# POWER.net
KiCad netlist of a schematic drawn in Altium Designer
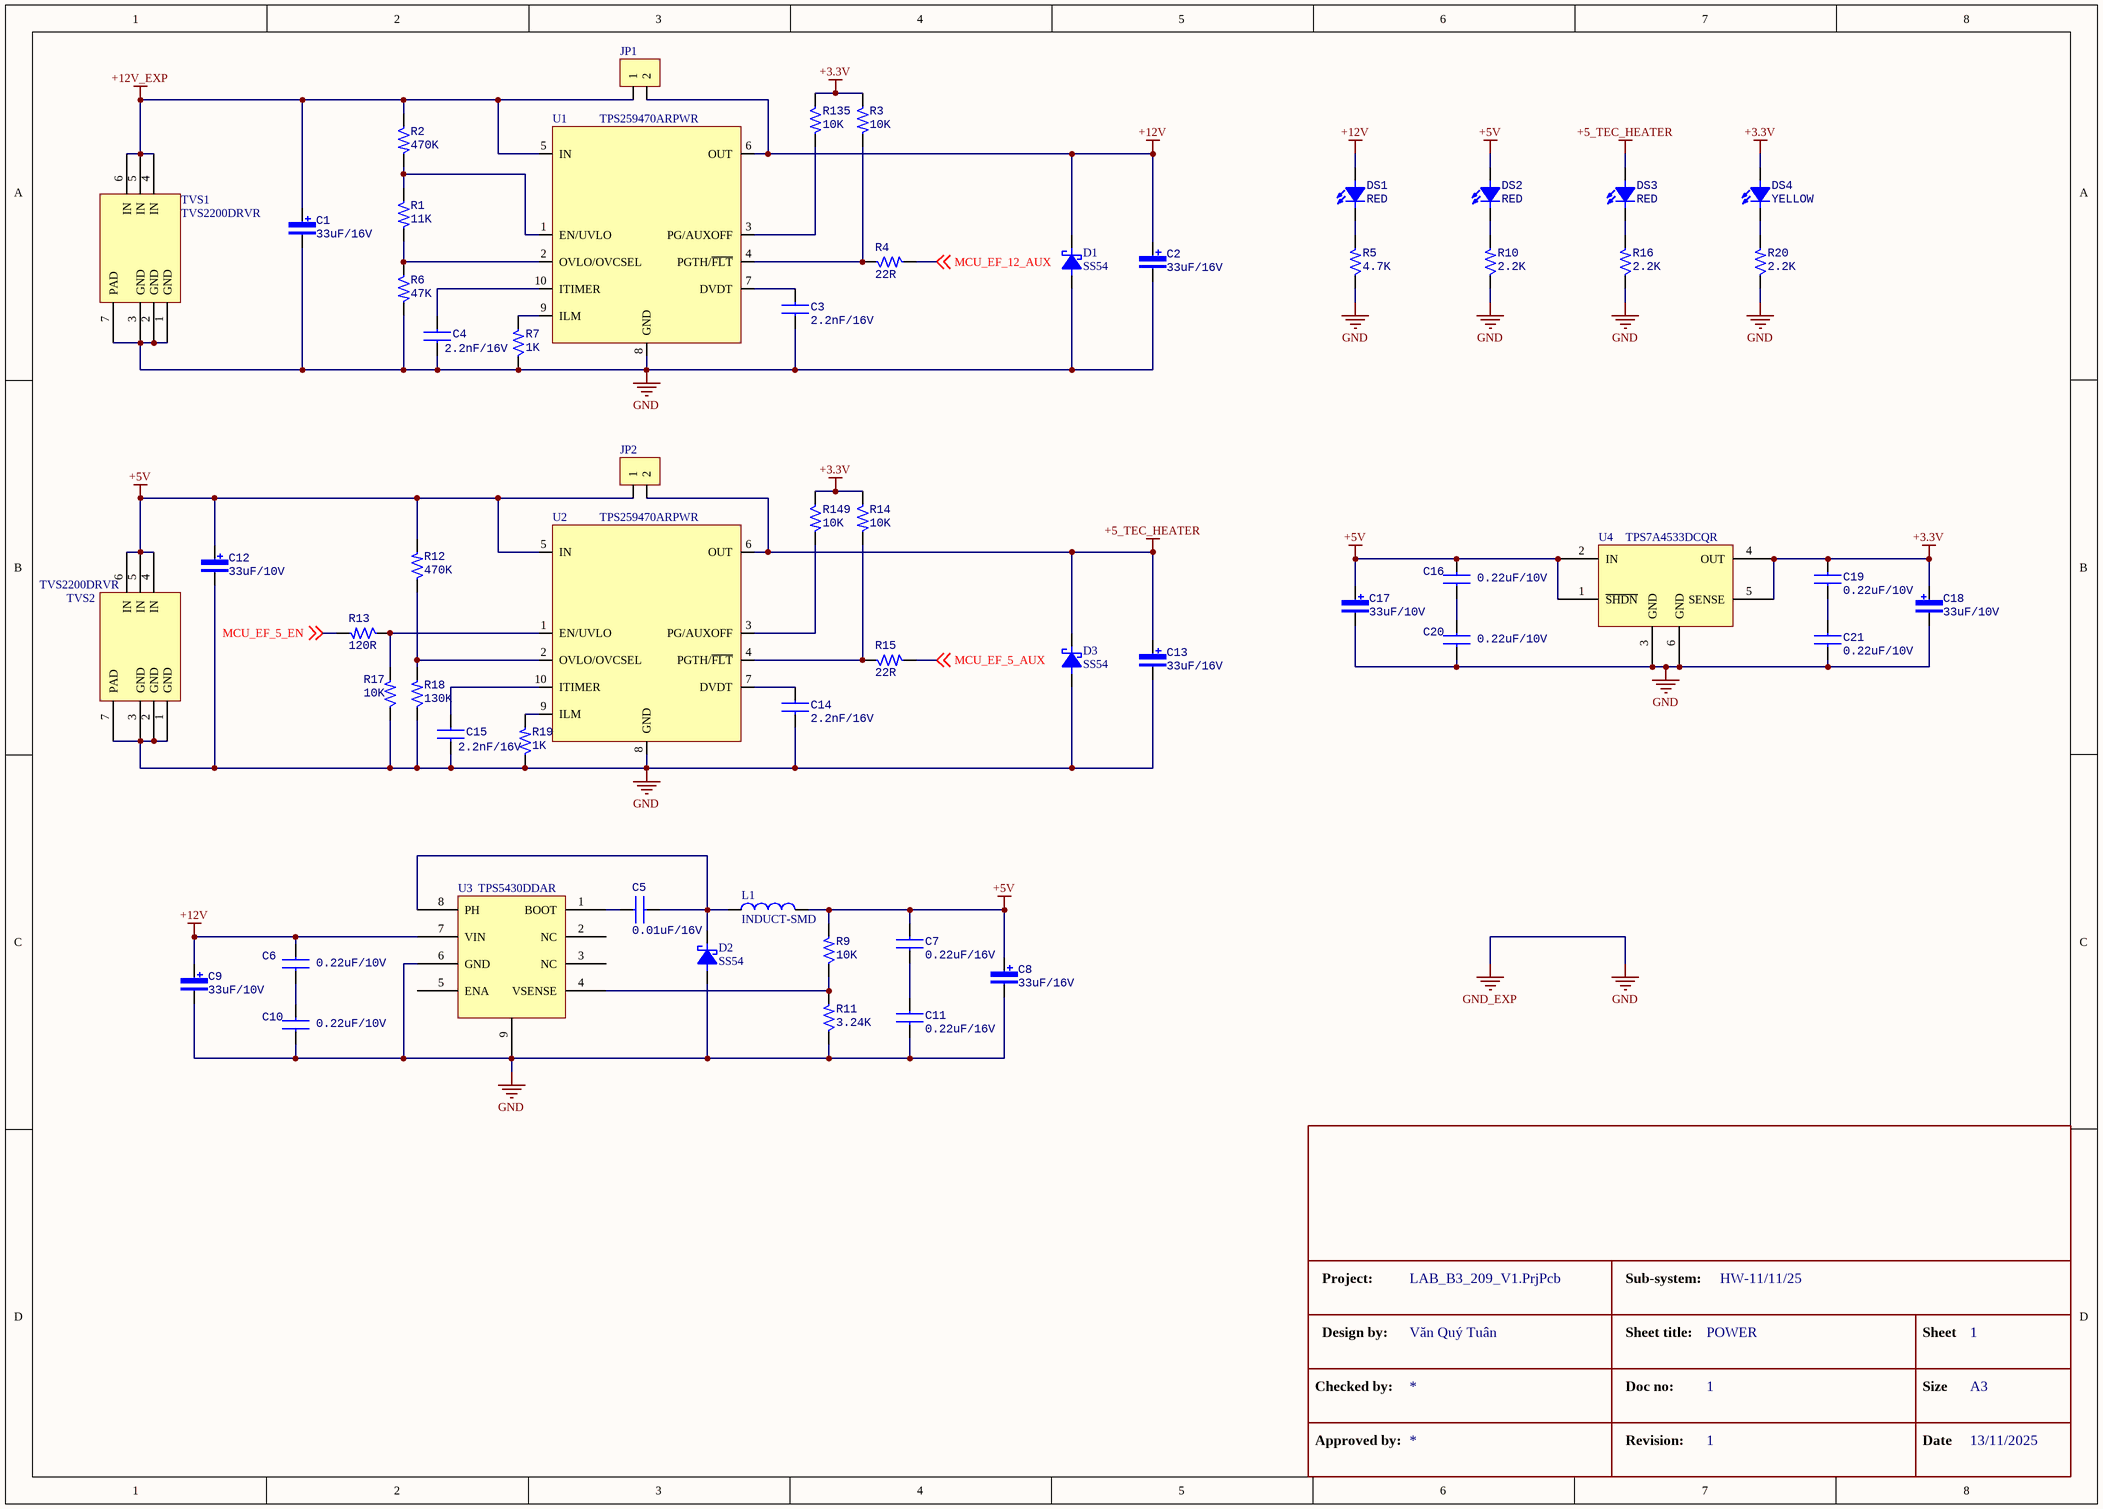
[diagram p0: POWER.SchDoc]

(export (version "E")
  (design (tool "Eeschema 10.0.6"))
  (components
    (comp (ref "C1") (value "33uF/16V") (footprint "CAP-TAN-2312") (libsource (lib "") (part "CAP-TAN_1")))
    (comp (ref "C2") (value "33uF/16V") (footprint "CAP-TAN-2312") (libsource (lib "") (part "CAP-TAN_1")))
    (comp (ref "C3") (value "2.2nF/16V") (footprint "CAP-CER-0603") (libsource (lib "ID") (part "CAP-CER")))
    (comp (ref "C4") (value "2.2nF/16V") (footprint "CAP-CER-0603") (libsource (lib "ID") (part "CAP-CER")))
    (comp (ref "C5") (value "0.01uF/16V") (footprint "CAP-CER-0603") (libsource (lib "ID") (part "CAP-CER")))
    (comp (ref "C6") (value "0.22uF/10V") (footprint "CAP-CER-0603") (libsource (lib "ID") (part "CAP-CER")))
    (comp (ref "C7") (value "0.22uF/16V") (footprint "CAP-CER-0603") (libsource (lib "ID") (part "CAP-CER")))
    (comp (ref "C8") (value "33uF/16V") (footprint "CAP-TAN-2312") (libsource (lib "") (part "CAP-TAN_1")))
    (comp (ref "C9") (value "33uF/10V") (footprint "CAP-TAN-2312") (libsource (lib "") (part "CAP-TAN_1")))
    (comp (ref "C10") (value "0.22uF/10V") (footprint "CAP-CER-0603") (libsource (lib "ID") (part "CAP-CER")))
    (comp (ref "C11") (value "0.22uF/16V") (footprint "CAP-CER-0603") (libsource (lib "ID") (part "CAP-CER")))
    (comp (ref "C12") (value "33uF/10V") (footprint "CAP-TAN-2312") (libsource (lib "") (part "CAP-TAN_1")))
    (comp (ref "C13") (value "33uF/16V") (footprint "CAP-TAN-2312") (libsource (lib "") (part "CAP-TAN_1")))
    (comp (ref "C14") (value "2.2nF/16V") (footprint "CAP-CER-0603") (libsource (lib "ID") (part "CAP-CER")))
    (comp (ref "C15") (value "2.2nF/16V") (footprint "CAP-CER-0603") (libsource (lib "ID") (part "CAP-CER")))
    (comp (ref "C16") (value "0.22uF/10V") (footprint "CAP-CER-0603") (libsource (lib "ID") (part "CAP-CER")))
    (comp (ref "C17") (value "33uF/10V") (footprint "CAP-TAN-2312") (libsource (lib "") (part "CAP-TAN_1")))
    (comp (ref "C18") (value "33uF/10V") (footprint "CAP-TAN-2312") (libsource (lib "ID") (part "CAP-TAN")))
    (comp (ref "C19") (value "0.22uF/10V") (footprint "CAP-CER-0603") (libsource (lib "ID") (part "CAP-CER")))
    (comp (ref "C20") (value "0.22uF/10V") (footprint "CAP-CER-0603") (libsource (lib "ID") (part "CAP-CER")))
    (comp (ref "C21") (value "0.22uF/10V") (footprint "CAP-CER-0603") (libsource (lib "ID") (part "CAP-CER")))
    (comp (ref "D1") (value "SS54") (footprint "DIODE SMA") (libsource (lib "ID") (part "DIODE-SCHOTTKY")))
    (comp (ref "D2") (value "SS54") (footprint "DIODE SMA") (libsource (lib "ID") (part "DIODE-SCHOTTKY")))
    (comp (ref "D3") (value "SS54") (footprint "DIODE SMA") (libsource (lib "ID") (part "DIODE-SCHOTTKY")))
    (comp (ref "DS1") (value "RED") (footprint "LED-SMD-0603") (libsource (lib "ID") (part "LED")))
    (comp (ref "DS2") (value "RED") (footprint "LED-SMD-0603") (libsource (lib "ID") (part "LED")))
    (comp (ref "DS3") (value "RED") (footprint "LED-SMD-0603") (libsource (lib "ID") (part "LED")))
    (comp (ref "DS4") (value "YELLOW") (footprint "LED-SMD-0603") (libsource (lib "ID") (part "LED")))
    (comp (ref "JP1")
      (value "JP 1x2 2.54")
      (footprint "JP 1x2 DT")
      (description "Cắm")
      (libsource (lib "Jump") (part "JP 1x2 2.54 Duc Thang"))
    )
    (comp (ref "JP2")
      (value "JP 1x2 2.54")
      (footprint "JP 1x2 DT")
      (description "Cắm")
      (libsource (lib "Jump") (part "JP 1x2 2.54 Duc Thang"))
    )
    (comp (ref "L1")
      (value "INDUCT-SMD")
      (footprint "INDUCTOR-FIXED IND 22UH 2.5A 170 MOHM SMD")
      (fields (field (name "MP") "LQM18PZ2R2MFHD") (field (name "MF") "Murata"))
      (libsource (lib "ID") (part "INDUCT-SMD"))
    )
    (comp (ref "R1") (value "11K") (footprint "RES-SMD-0603") (libsource (lib "ID") (part "RES-SMD")))
    (comp (ref "R2") (value "470K") (footprint "RES-SMD-0603") (libsource (lib "ID") (part "RES-SMD")))
    (comp (ref "R3") (value "10K") (footprint "RES-SMD-0603") (libsource (lib "ID") (part "RES-SMD")))
    (comp (ref "R4") (value "22R") (footprint "RES-SMD-0603") (libsource (lib "ID") (part "RES-SMD")))
    (comp (ref "R5") (value "4.7K") (footprint "RES-SMD-0603") (libsource (lib "ID") (part "RES-SMD")))
    (comp (ref "R6") (value "47K") (footprint "RES-SMD-0603") (libsource (lib "ID") (part "RES-SMD")))
    (comp (ref "R7") (value "1K") (footprint "RES-SMD-0603") (libsource (lib "ID") (part "RES-SMD")))
    (comp (ref "R9") (value "10K") (footprint "RES-SMD-0603") (libsource (lib "ID") (part "RES-SMD")))
    (comp (ref "R10") (value "2.2K") (footprint "RES-SMD-0603") (libsource (lib "ID") (part "RES-SMD")))
    (comp (ref "R11") (value "3.24K") (footprint "RES-SMD-0603") (libsource (lib "ID") (part "RES-SMD")))
    (comp (ref "R12") (value "470K") (footprint "RES-SMD-0603") (libsource (lib "ID") (part "RES-SMD")))
    (comp (ref "R13") (value "120R") (footprint "RES-SMD-0603") (libsource (lib "ID") (part "RES-SMD")))
    (comp (ref "R14") (value "10K") (footprint "RES-SMD-0603") (libsource (lib "ID") (part "RES-SMD")))
    (comp (ref "R15") (value "22R") (footprint "RES-SMD-0603") (libsource (lib "ID") (part "RES-SMD")))
    (comp (ref "R16") (value "2.2K") (footprint "RES-SMD-0603") (libsource (lib "ID") (part "RES-SMD")))
    (comp (ref "R17") (value "10K") (footprint "RES-SMD-0603") (libsource (lib "ID") (part "RES-SMD")))
    (comp (ref "R18") (value "130K") (footprint "RES-SMD-0603") (libsource (lib "ID") (part "RES-SMD")))
    (comp (ref "R19") (value "1K") (footprint "RES-SMD-0603") (libsource (lib "ID") (part "RES-SMD")))
    (comp (ref "R20") (value "2.2K") (footprint "RES-SMD-0603") (libsource (lib "ID") (part "RES-SMD")))
    (comp (ref "R135") (value "10K") (footprint "RES-SMD-0603") (libsource (lib "ID") (part "RES-SMD")))
    (comp (ref "R149") (value "10K") (footprint "RES-SMD-0603") (libsource (lib "ID") (part "RES-SMD")))
    (comp (ref "TVS1")
      (value "TVS2200DRVR")
      (footprint "TVS2200DRVR")
      (libsource (lib "LAB_B3_209_V1") (part "TVS2200DRVR"))
    )
    (comp (ref "TVS2")
      (value "TVS2200DRVR")
      (footprint "TVS2200DRVR")
      (libsource (lib "LAB_B3_209_V1") (part "TVS2200DRVR"))
    )
    (comp (ref "U1")
      (value "TPS259470ARPWR")
      (footprint "VQFN-HR-10")
      (fields
        (field (name "MANUFACTURER") "Texas Instruments")
        (field (name "MANUFACTURER PART NUMBER") "TPS259472ARPWR")
      )
      (libsource (lib "Schematic-Lib-PhilsLab") (part "TPS259472ARPWR"))
    )
    (comp (ref "U2")
      (value "TPS259470ARPWR")
      (footprint "VQFN-HR-10")
      (fields
        (field (name "MANUFACTURER") "Texas Instruments")
        (field (name "MANUFACTURER PART NUMBER") "TPS259472ARPWR")
      )
      (libsource (lib "Schematic-Lib-PhilsLab") (part "TPS259472ARPWR"))
    )
    (comp (ref "U3")
      (value "TPS5430DDAR")
      (footprint "TPS5430DDAR")
      (libsource (lib "LAB_B3_209_V1") (part "TPS5430DDAR"))
    )
    (comp (ref "U4")
      (value "TPS7A4533DCQR")
      (footprint "TPS7A4533DCQR")
      (libsource (lib "LAB_B3_209_V1") (part "TPS7A4533DCQR"))
    )
  )
  (nets
    (net (code "1") (name "+3.3V") (class "Default")
      (node (ref "C18") (pin "1") (pinfunction "1_1") (pintype "passive"))
      (node (ref "C19") (pin "2") (pinfunction "2_2") (pintype "passive"))
      (node (ref "DS4") (pin "A") (pinfunction "A_A") (pintype "passive"))
      (node (ref "R135") (pin "1") (pinfunction "1_1") (pintype "passive"))
      (node (ref "R14") (pin "1") (pinfunction "1_1") (pintype "passive"))
      (node (ref "R149") (pin "1") (pinfunction "1_1") (pintype "passive"))
      (node (ref "R3") (pin "1") (pinfunction "1_1") (pintype "passive"))
      (node (ref "U4") (pin "4") (pinfunction "OUT_4") (pintype "passive"))
      (node (ref "U4") (pin "5") (pinfunction "SENSE_5") (pintype "passive"))
    )
    (net (code "2") (name "+5V") (class "Default")
      (node (ref "C12") (pin "1") (pinfunction "1_1") (pintype "passive"))
      (node (ref "C16") (pin "2") (pinfunction "2_2") (pintype "passive"))
      (node (ref "C17") (pin "1") (pinfunction "1_1") (pintype "passive"))
      (node (ref "C7") (pin "1") (pinfunction "1_1") (pintype "passive"))
      (node (ref "C8") (pin "1") (pinfunction "1_1") (pintype "passive"))
      (node (ref "DS2") (pin "A") (pinfunction "A_A") (pintype "passive"))
      (node (ref "JP2") (pin "1") (pinfunction "1_1") (pintype "passive"))
      (node (ref "L1") (pin "2") (pinfunction "2_2") (pintype "passive"))
      (node (ref "R12") (pin "2") (pinfunction "2_2") (pintype "passive"))
      (node (ref "R9") (pin "2") (pinfunction "2_2") (pintype "passive"))
      (node (ref "TVS2") (pin "4") (pinfunction "IN_4") (pintype "passive"))
      (node (ref "TVS2") (pin "5") (pinfunction "IN_5") (pintype "passive"))
      (node (ref "TVS2") (pin "6") (pinfunction "IN_6") (pintype "passive"))
      (node (ref "U2") (pin "5") (pinfunction "IN_5") (pintype "passive"))
      (node (ref "U4") (pin "1") (pinfunction "~{SHDN}_1") (pintype "passive"))
      (node (ref "U4") (pin "2") (pinfunction "IN_2") (pintype "passive"))
    )
    (net (code "3") (name "+5_TEC_HEATER") (class "Default")
      (node (ref "C13") (pin "1") (pinfunction "1_1") (pintype "passive"))
      (node (ref "D3") (pin "2") (pinfunction "K_2") (pintype "passive"))
      (node (ref "DS3") (pin "A") (pinfunction "A_A") (pintype "passive"))
      (node (ref "JP2") (pin "2") (pinfunction "2_2") (pintype "passive"))
      (node (ref "U2") (pin "6") (pinfunction "OUT_6") (pintype "passive"))
    )
    (net (code "4") (name "+12V") (class "Default")
      (node (ref "C2") (pin "1") (pinfunction "1_1") (pintype "passive"))
      (node (ref "C6") (pin "2") (pinfunction "2_2") (pintype "passive"))
      (node (ref "C9") (pin "1") (pinfunction "1_1") (pintype "passive"))
      (node (ref "D1") (pin "2") (pinfunction "K_2") (pintype "passive"))
      (node (ref "DS1") (pin "A") (pinfunction "A_A") (pintype "passive"))
      (node (ref "JP1") (pin "2") (pinfunction "2_2") (pintype "passive"))
      (node (ref "U1") (pin "6") (pinfunction "OUT_6") (pintype "passive"))
      (node (ref "U3") (pin "7") (pinfunction "VIN_7") (pintype "passive"))
    )
    (net (code "5") (name "+12V_EXP") (class "Default")
      (node (ref "C1") (pin "1") (pinfunction "1_1") (pintype "passive"))
      (node (ref "JP1") (pin "1") (pinfunction "1_1") (pintype "passive"))
      (node (ref "R2") (pin "1") (pinfunction "1_1") (pintype "passive"))
      (node (ref "TVS1") (pin "4") (pinfunction "IN_4") (pintype "passive"))
      (node (ref "TVS1") (pin "5") (pinfunction "IN_5") (pintype "passive"))
      (node (ref "TVS1") (pin "6") (pinfunction "IN_6") (pintype "passive"))
      (node (ref "U1") (pin "5") (pinfunction "IN_5") (pintype "passive"))
    )
    (net (code "6") (name "GND") (class "Default")
      (node (ref "C1") (pin "2") (pinfunction "2_2") (pintype "passive"))
      (node (ref "C10") (pin "1") (pinfunction "1_1") (pintype "passive"))
      (node (ref "C11") (pin "2") (pinfunction "2_2") (pintype "passive"))
      (node (ref "C12") (pin "2") (pinfunction "2_2") (pintype "passive"))
      (node (ref "C13") (pin "2") (pinfunction "2_2") (pintype "passive"))
      (node (ref "C14") (pin "1") (pinfunction "1_1") (pintype "passive"))
      (node (ref "C15") (pin "1") (pinfunction "1_1") (pintype "passive"))
      (node (ref "C17") (pin "2") (pinfunction "2_2") (pintype "passive"))
      (node (ref "C18") (pin "2") (pinfunction "2_2") (pintype "passive"))
      (node (ref "C2") (pin "2") (pinfunction "2_2") (pintype "passive"))
      (node (ref "C20") (pin "1") (pinfunction "1_1") (pintype "passive"))
      (node (ref "C21") (pin "1") (pinfunction "1_1") (pintype "passive"))
      (node (ref "C3") (pin "1") (pinfunction "1_1") (pintype "passive"))
      (node (ref "C4") (pin "1") (pinfunction "1_1") (pintype "passive"))
      (node (ref "C8") (pin "2") (pinfunction "2_2") (pintype "passive"))
      (node (ref "C9") (pin "2") (pinfunction "2_2") (pintype "passive"))
      (node (ref "D1") (pin "1") (pinfunction "A_1") (pintype "passive"))
      (node (ref "D2") (pin "1") (pinfunction "A_1") (pintype "passive"))
      (node (ref "D3") (pin "1") (pinfunction "A_1") (pintype "passive"))
      (node (ref "R10") (pin "1") (pinfunction "1_1") (pintype "passive"))
      (node (ref "R11") (pin "1") (pinfunction "1_1") (pintype "passive"))
      (node (ref "R16") (pin "1") (pinfunction "1_1") (pintype "passive"))
      (node (ref "R17") (pin "1") (pinfunction "1_1") (pintype "passive"))
      (node (ref "R18") (pin "1") (pinfunction "1_1") (pintype "passive"))
      (node (ref "R19") (pin "1") (pinfunction "1_1") (pintype "passive"))
      (node (ref "R20") (pin "1") (pinfunction "1_1") (pintype "passive"))
      (node (ref "R5") (pin "1") (pinfunction "1_1") (pintype "passive"))
      (node (ref "R6") (pin "2") (pinfunction "2_2") (pintype "passive"))
      (node (ref "R7") (pin "1") (pinfunction "1_1") (pintype "passive"))
      (node (ref "TVS1") (pin "1") (pinfunction "GND_1") (pintype "passive"))
      (node (ref "TVS1") (pin "2") (pinfunction "GND_2") (pintype "passive"))
      (node (ref "TVS1") (pin "3") (pinfunction "GND_3") (pintype "passive"))
      (node (ref "TVS1") (pin "7") (pinfunction "PAD_7") (pintype "passive"))
      (node (ref "TVS2") (pin "1") (pinfunction "GND_1") (pintype "passive"))
      (node (ref "TVS2") (pin "2") (pinfunction "GND_2") (pintype "passive"))
      (node (ref "TVS2") (pin "3") (pinfunction "GND_3") (pintype "passive"))
      (node (ref "TVS2") (pin "7") (pinfunction "PAD_7") (pintype "passive"))
      (node (ref "U1") (pin "8") (pinfunction "GND_8") (pintype "passive"))
      (node (ref "U2") (pin "8") (pinfunction "GND_8") (pintype "passive"))
      (node (ref "U3") (pin "6") (pinfunction "GND_6") (pintype "passive"))
      (node (ref "U3") (pin "9") (pinfunction "PAD_9") (pintype "passive"))
      (node (ref "U4") (pin "3") (pinfunction "GND_3") (pintype "passive"))
      (node (ref "U4") (pin "6") (pinfunction "GND_6") (pintype "passive"))
    )
    (net (code "7") (name "MCU_EF_5_AUX") (class "Default")
      (node (ref "R15") (pin "2") (pinfunction "2_2") (pintype "passive"))
    )
    (net (code "8") (name "MCU_EF_5_EN") (class "Default")
      (node (ref "R13") (pin "2") (pinfunction "2_2") (pintype "passive"))
    )
    (net (code "9") (name "MCU_EF_12_AUX") (class "Default")
      (node (ref "R4") (pin "2") (pinfunction "2_2") (pintype "passive"))
    )
    (net (code "10") (name "Net-(C10-Pad2)") (class "Default")
      (node (ref "C10") (pin "2") (pinfunction "2_2") (pintype "passive"))
      (node (ref "C6") (pin "1") (pinfunction "1_1") (pintype "passive"))
    )
    (net (code "11") (name "Net-(C11-Pad1)") (class "Default")
      (node (ref "C11") (pin "1") (pinfunction "1_1") (pintype "passive"))
      (node (ref "C7") (pin "2") (pinfunction "2_2") (pintype "passive"))
    )
    (net (code "12") (name "Net-(C16-Pad1)") (class "Default")
      (node (ref "C16") (pin "1") (pinfunction "1_1") (pintype "passive"))
      (node (ref "C20") (pin "2") (pinfunction "2_2") (pintype "passive"))
    )
    (net (code "13") (name "Net-(C19-Pad1)") (class "Default")
      (node (ref "C19") (pin "1") (pinfunction "1_1") (pintype "passive"))
      (node (ref "C21") (pin "2") (pinfunction "2_2") (pintype "passive"))
    )
    (net (code "14") (name "Net-(D2-K)") (class "Default")
      (node (ref "C5") (pin "1") (pinfunction "1_1") (pintype "passive"))
      (node (ref "D2") (pin "2") (pinfunction "K_2") (pintype "passive"))
      (node (ref "L1") (pin "1") (pinfunction "1_1") (pintype "passive"))
      (node (ref "U3") (pin "8") (pinfunction "PH_8") (pintype "passive"))
    )
    (net (code "15") (name "Net-(DS1-PadK)") (class "Default")
      (node (ref "DS1") (pin "K") (pinfunction "K_K") (pintype "passive"))
      (node (ref "R5") (pin "2") (pinfunction "2_2") (pintype "passive"))
    )
    (net (code "16") (name "Net-(DS2-PadK)") (class "Default")
      (node (ref "DS2") (pin "K") (pinfunction "K_K") (pintype "passive"))
      (node (ref "R10") (pin "2") (pinfunction "2_2") (pintype "passive"))
    )
    (net (code "17") (name "Net-(DS3-PadK)") (class "Default")
      (node (ref "DS3") (pin "K") (pinfunction "K_K") (pintype "passive"))
      (node (ref "R16") (pin "2") (pinfunction "2_2") (pintype "passive"))
    )
    (net (code "18") (name "Net-(DS4-PadK)") (class "Default")
      (node (ref "DS4") (pin "K") (pinfunction "K_K") (pintype "passive"))
      (node (ref "R20") (pin "2") (pinfunction "2_2") (pintype "passive"))
    )
    (net (code "19") (name "Net-(U1-DVDT)") (class "Default")
      (node (ref "C3") (pin "2") (pinfunction "2_2") (pintype "passive"))
      (node (ref "U1") (pin "7") (pinfunction "DVDT_7") (pintype "passive"))
    )
    (net (code "20") (name "Net-(U1-EN{slash}UVLO)") (class "Default")
      (node (ref "R1") (pin "1") (pinfunction "1_1") (pintype "passive"))
      (node (ref "R2") (pin "2") (pinfunction "2_2") (pintype "passive"))
      (node (ref "U1") (pin "1") (pinfunction "EN/UVLO_1") (pintype "passive"))
    )
    (net (code "21") (name "Net-(U1-ILM)") (class "Default")
      (node (ref "R7") (pin "2") (pinfunction "2_2") (pintype "passive"))
      (node (ref "U1") (pin "9") (pinfunction "ILM_9") (pintype "passive"))
    )
    (net (code "22") (name "Net-(U1-ITIMER)") (class "Default")
      (node (ref "C4") (pin "2") (pinfunction "2_2") (pintype "passive"))
      (node (ref "U1") (pin "10") (pinfunction "ITIMER_10") (pintype "passive"))
    )
    (net (code "23") (name "Net-(U1-OVLO{slash}OVCSEL)") (class "Default")
      (node (ref "R1") (pin "2") (pinfunction "2_2") (pintype "passive"))
      (node (ref "R6") (pin "1") (pinfunction "1_1") (pintype "passive"))
      (node (ref "U1") (pin "2") (pinfunction "OVLO/OVCSEL_2") (pintype "passive"))
    )
    (net (code "24") (name "Net-(U1-PGTH{slash}~{FLT})") (class "Default")
      (node (ref "R3") (pin "2") (pinfunction "2_2") (pintype "passive"))
      (node (ref "R4") (pin "1") (pinfunction "1_1") (pintype "passive"))
      (node (ref "U1") (pin "4") (pinfunction "PGTH/~{FLT}_4") (pintype "passive"))
    )
    (net (code "25") (name "Net-(U1-PG{slash}AUXOFF)") (class "Default")
      (node (ref "R135") (pin "2") (pinfunction "2_2") (pintype "passive"))
      (node (ref "U1") (pin "3") (pinfunction "PG/AUXOFF_3") (pintype "passive"))
    )
    (net (code "26") (name "Net-(U2-DVDT)") (class "Default")
      (node (ref "C14") (pin "2") (pinfunction "2_2") (pintype "passive"))
      (node (ref "U2") (pin "7") (pinfunction "DVDT_7") (pintype "passive"))
    )
    (net (code "27") (name "Net-(U2-EN{slash}UVLO)") (class "Default")
      (node (ref "R13") (pin "1") (pinfunction "1_1") (pintype "passive"))
      (node (ref "R17") (pin "2") (pinfunction "2_2") (pintype "passive"))
      (node (ref "U2") (pin "1") (pinfunction "EN/UVLO_1") (pintype "passive"))
    )
    (net (code "28") (name "Net-(U2-ILM)") (class "Default")
      (node (ref "R19") (pin "2") (pinfunction "2_2") (pintype "passive"))
      (node (ref "U2") (pin "9") (pinfunction "ILM_9") (pintype "passive"))
    )
    (net (code "29") (name "Net-(U2-ITIMER)") (class "Default")
      (node (ref "C15") (pin "2") (pinfunction "2_2") (pintype "passive"))
      (node (ref "U2") (pin "10") (pinfunction "ITIMER_10") (pintype "passive"))
    )
    (net (code "30") (name "Net-(U2-OVLO{slash}OVCSEL)") (class "Default")
      (node (ref "R12") (pin "1") (pinfunction "1_1") (pintype "passive"))
      (node (ref "R18") (pin "2") (pinfunction "2_2") (pintype "passive"))
      (node (ref "U2") (pin "2") (pinfunction "OVLO/OVCSEL_2") (pintype "passive"))
    )
    (net (code "31") (name "Net-(U2-PGTH{slash}~{FLT})") (class "Default")
      (node (ref "R14") (pin "2") (pinfunction "2_2") (pintype "passive"))
      (node (ref "R15") (pin "1") (pinfunction "1_1") (pintype "passive"))
      (node (ref "U2") (pin "4") (pinfunction "PGTH/~{FLT}_4") (pintype "passive"))
    )
    (net (code "32") (name "Net-(U2-PG{slash}AUXOFF)") (class "Default")
      (node (ref "R149") (pin "2") (pinfunction "2_2") (pintype "passive"))
      (node (ref "U2") (pin "3") (pinfunction "PG/AUXOFF_3") (pintype "passive"))
    )
    (net (code "33") (name "Net-(U3-BOOT)") (class "Default")
      (node (ref "C5") (pin "2") (pinfunction "2_2") (pintype "passive"))
      (node (ref "U3") (pin "1") (pinfunction "BOOT_1") (pintype "passive"))
    )
    (net (code "34") (name "Net-(U3-VSENSE)") (class "Default")
      (node (ref "R11") (pin "2") (pinfunction "2_2") (pintype "passive"))
      (node (ref "R9") (pin "1") (pinfunction "1_1") (pintype "passive"))
      (node (ref "U3") (pin "4") (pinfunction "VSENSE_4") (pintype "passive"))
    )
    (net (code "35") (name "unconnected-(U3-ENA-Pad5)") (class "Default")
      (node (ref "U3") (pin "5") (pinfunction "ENA_5") (pintype "passive"))
    )
    (net (code "36") (name "unconnected-(U3-NC-Pad2)") (class "Default")
      (node (ref "U3") (pin "2") (pinfunction "NC_2") (pintype "passive"))
    )
    (net (code "37") (name "unconnected-(U3-NC-Pad3)") (class "Default")
      (node (ref "U3") (pin "3") (pinfunction "NC_3") (pintype "passive"))
    )
  )
)
